# OOBDROID_V1.net
KiCad netlist of a schematic drawn in EAGLE
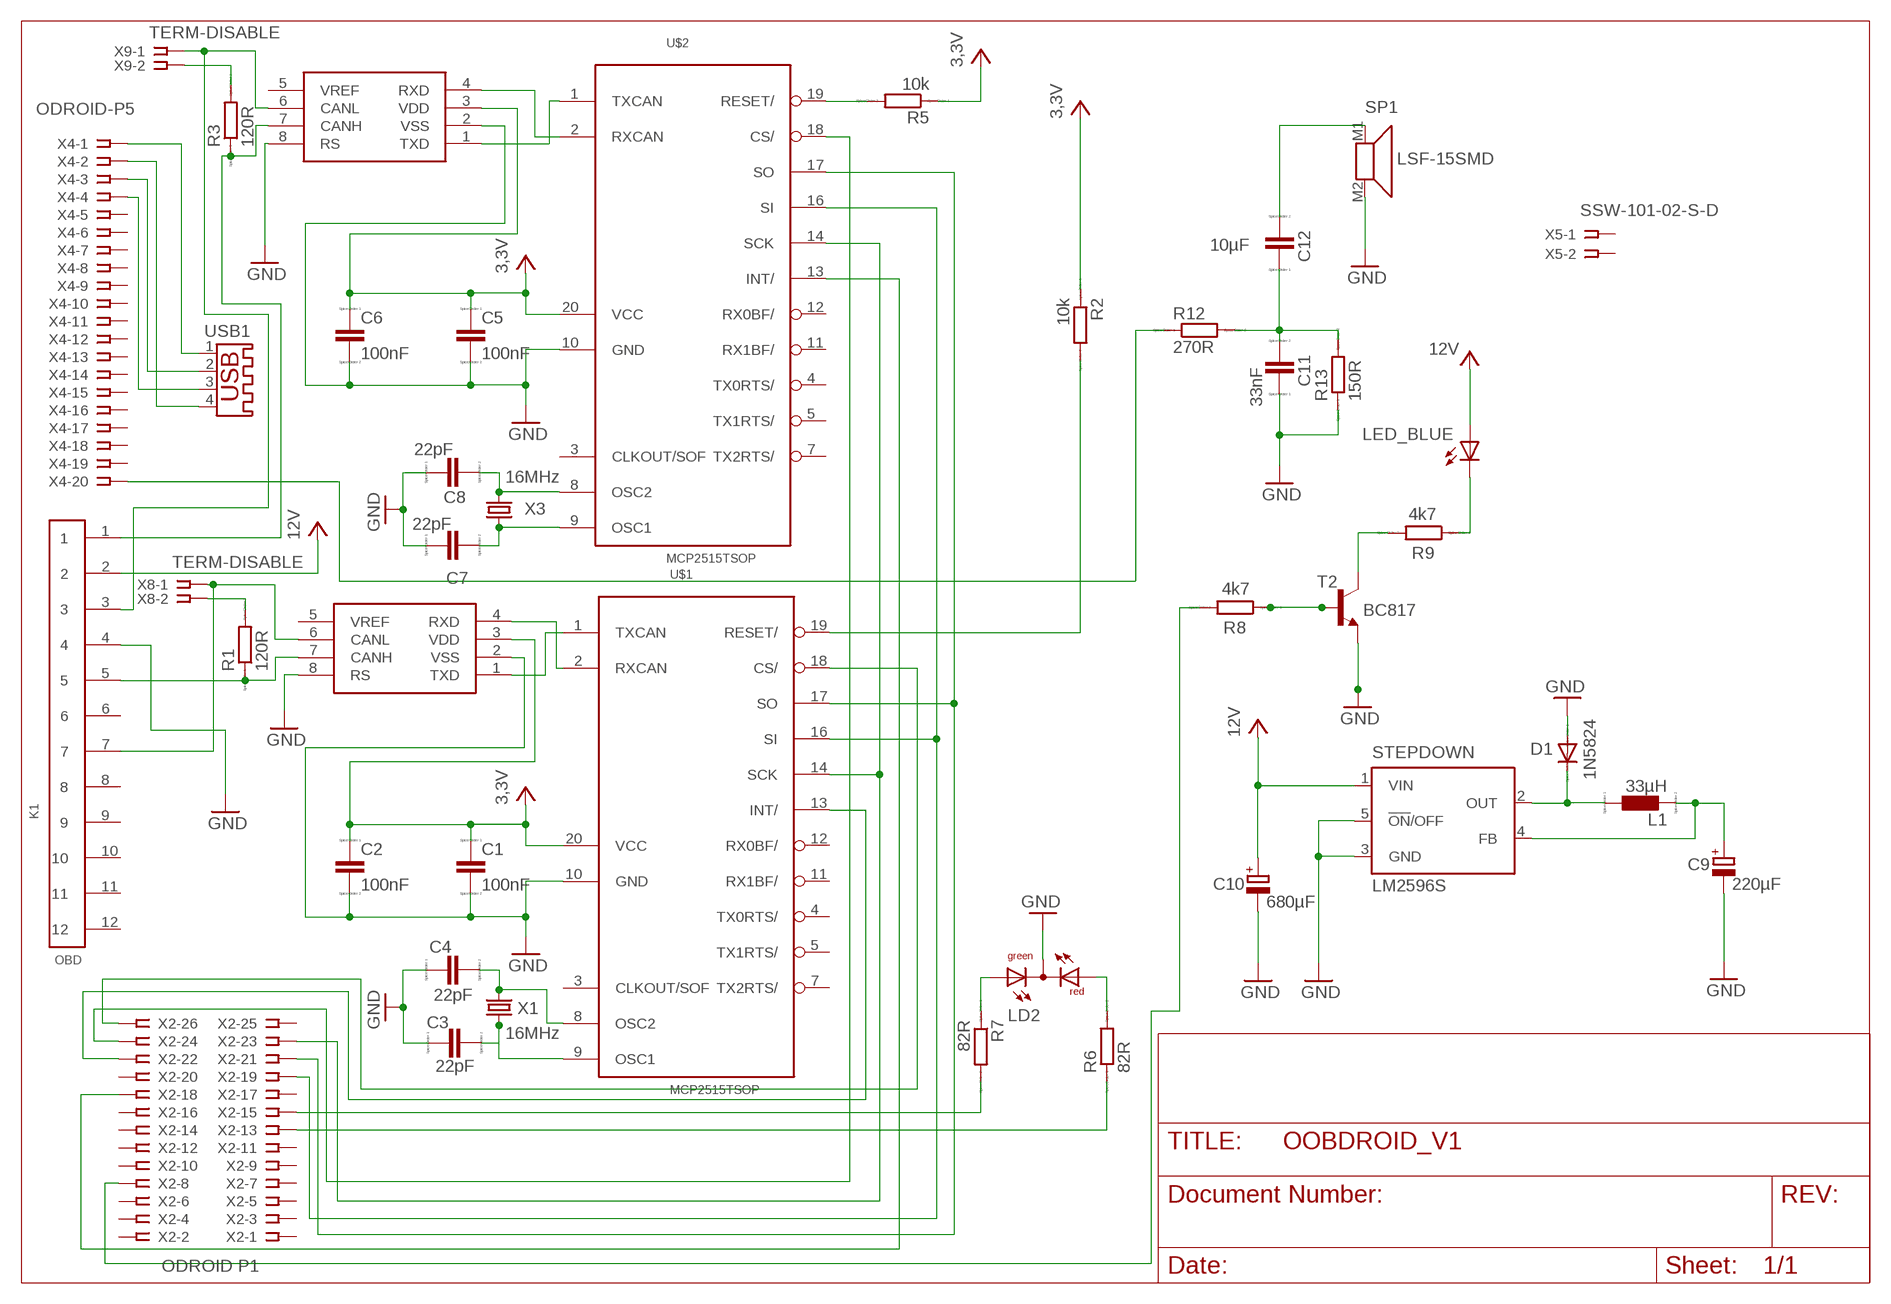
[diagram p0: schematic, sheet 1]

(export (version "E")
  (design (tool "Eeschema 10.0.6"))
  (components
    (comp (ref "C1")
      (value "100nF")
      (footprint "eagle-import:C0805")
      (libsource (lib "eagle-import") (part "C"))
    )
    (comp (ref "C2")
      (value "100nF")
      (footprint "eagle-import:C0805")
      (libsource (lib "eagle-import") (part "C"))
    )
    (comp (ref "C3")
      (value "22pF")
      (footprint "eagle-import:C0805")
      (libsource (lib "eagle-import") (part "C"))
    )
    (comp (ref "C4")
      (value "22pF")
      (footprint "eagle-import:C0805")
      (libsource (lib "eagle-import") (part "C"))
    )
    (comp (ref "C5")
      (value "100nF")
      (footprint "eagle-import:C0805")
      (libsource (lib "eagle-import") (part "C"))
    )
    (comp (ref "C6")
      (value "100nF")
      (footprint "eagle-import:C0805")
      (libsource (lib "eagle-import") (part "C"))
    )
    (comp (ref "C7")
      (value "22pF")
      (footprint "eagle-import:C0805")
      (libsource (lib "eagle-import") (part "C"))
    )
    (comp (ref "C8")
      (value "22pF")
      (footprint "eagle-import:C0805")
      (libsource (lib "eagle-import") (part "C"))
    )
    (comp (ref "C9")
      (value "220µF")
      (footprint "eagle-import:E1,8-4")
      (libsource (lib "eagle-import") (part "CPOL-EUE1.8-4"))
    )
    (comp (ref "C10")
      (value "680µF")
      (footprint "eagle-import:E1,8-4")
      (libsource (lib "eagle-import") (part "CPOL-EUE1.8-4"))
    )
    (comp (ref "C11")
      (value "33nF")
      (footprint "eagle-import:C0805")
      (libsource (lib "eagle-import") (part "C"))
    )
    (comp (ref "C12")
      (value "10µF")
      (footprint "eagle-import:C0805")
      (libsource (lib "eagle-import") (part "C"))
    )
    (comp (ref "D1")
      (value "1N5824")
      (footprint "eagle-import:DO214AA")
      (libsource (lib "eagle-import") (part "DIODE-DO214AA"))
    )
    (comp (ref "K1")
      (value "OBD")
      (footprint "eagle-import:653112124022")
      (libsource (lib "eagle-import") (part "653112124022"))
    )
    (comp (ref "L1")
      (value "33µH")
      (footprint "eagle-import:L4532P")
      (libsource (lib "eagle-import") (part "LL4532P"))
    )
    (comp (ref "LD2")
      (value "DUOLED-RG-C")
      (footprint "eagle-import:DUOLED-C-5MM")
      (libsource (lib "eagle-import") (part "DUOLED-RG-C"))
    )
    (comp (ref "LED_BLUE")
      (value "LED5MM")
      (footprint "eagle-import:LED5MM")
      (libsource (lib "eagle-import") (part "LED5MM"))
    )
    (comp (ref "R1")
      (value "120R")
      (footprint "eagle-import:R0603")
      (libsource (lib "eagle-import") (part "RR0603"))
    )
    (comp (ref "R2")
      (value "10k")
      (footprint "eagle-import:R0603")
      (libsource (lib "eagle-import") (part "RR0603"))
    )
    (comp (ref "R3")
      (value "120R")
      (footprint "eagle-import:R0603")
      (libsource (lib "eagle-import") (part "RR0603"))
    )
    (comp (ref "R5")
      (value "10k")
      (footprint "eagle-import:R0603")
      (libsource (lib "eagle-import") (part "RR0603"))
    )
    (comp (ref "R6")
      (value "82R")
      (footprint "eagle-import:R0603")
      (libsource (lib "eagle-import") (part "RR0603"))
    )
    (comp (ref "R7")
      (value "82R")
      (footprint "eagle-import:R0603")
      (libsource (lib "eagle-import") (part "RR0603"))
    )
    (comp (ref "R8")
      (value "4k7")
      (footprint "eagle-import:R0603")
      (libsource (lib "eagle-import") (part "RR0603"))
    )
    (comp (ref "R9")
      (value "4k7")
      (footprint "eagle-import:R0603")
      (libsource (lib "eagle-import") (part "RR0603"))
    )
    (comp (ref "R12")
      (value "270R")
      (footprint "eagle-import:R0603")
      (libsource (lib "eagle-import") (part "RR0603"))
    )
    (comp (ref "R13")
      (value "150R")
      (footprint "eagle-import:R0603")
      (libsource (lib "eagle-import") (part "RR0603"))
    )
    (comp (ref "SP1")
      (value "LSF-15SMD")
      (footprint "eagle-import:SMS-1308MS-2-R")
      (libsource (lib "eagle-import") (part "SMS-1308MS-2-RLSF-15SMD"))
    )
    (comp (ref "STEPDOWN")
      (value "LM2596S")
      (footprint "eagle-import:TO263-5")
      (fields (field (name "MF") "NATIONAL SEMICONDUCTOR") (field (name "MPN") "LM2596S-ADJ/NOPB"))
      (libsource (lib "eagle-import") (part "LM2596S"))
    )
    (comp (ref "T2")
      (value "BC817")
      (footprint "eagle-import:SOT23")
      (libsource (lib "eagle-import") (part "BC847"))
    )
    (comp (ref "U$1")
      (value "MCP2515TSOP")
      (footprint "eagle-import:TSSOP20")
      (libsource (lib "eagle-import") (part "MCP2515TSOP"))
    )
    (comp (ref "U$2")
      (value "MCP2515TSOP")
      (footprint "eagle-import:TSSOP20")
      (libsource (lib "eagle-import") (part "MCP2515TSOP"))
    )
    (comp (ref "U1")
      (value "MCP2551")
      (footprint "eagle-import:SO08")
      (libsource (lib "eagle-import") (part "MCP2551"))
    )
    (comp (ref "U2")
      (value "MCP2551")
      (footprint "eagle-import:SO08")
      (libsource (lib "eagle-import") (part "MCP2551"))
    )
    (comp (ref "USB1")
      (value "USB-A003")
      (footprint "eagle-import:USB-A003")
      (libsource (lib "eagle-import") (part "USB-A003"))
    )
    (comp (ref "X1")
      (value "16MHz")
      (footprint "eagle-import:HC49")
      (libsource (lib "eagle-import") (part "CRYSTALS-NOGND-HC49"))
    )
    (comp (ref "X2")
      (value "ODROID P1")
      (footprint "eagle-import:SSW-113-02-S-D")
      (fields (field (name "MPN") "SSW-113-02-S-D"))
      (libsource (lib "eagle-import") (part "SSW-113-02-S-D"))
    )
    (comp (ref "X3")
      (value "16MHz")
      (footprint "eagle-import:HC49")
      (libsource (lib "eagle-import") (part "CRYSTALS-NOGND-HC49"))
    )
    (comp (ref "X4")
      (value "ODROID-P5")
      (footprint "eagle-import:SSW-120-02-S-S")
      (fields (field (name "MPN") "SSW-120-02-S-S"))
      (libsource (lib "eagle-import") (part "SSW-120-02-S-S"))
    )
    (comp (ref "X5")
      (value "SSW-101-02-S-D")
      (footprint "eagle-import:SSW-101-02-S-D")
      (libsource (lib "eagle-import") (part "SSW-101-02-S-D"))
    )
    (comp (ref "X8")
      (value "TERM-DISABLE")
      (footprint "eagle-import:SSW-101-02-S-D")
      (fields (field (name "MPN") "SSW-101-02-S-D") (field (name "MPN_1") "CAN-DISABLE"))
      (libsource (lib "eagle-import") (part "SSW-101-02-S-D"))
    )
    (comp (ref "X9")
      (value "TERM-DISABLE")
      (footprint "eagle-import:SSW-101-02-S-D")
      (fields (field (name "MPN") "SSW-101-02-S-D"))
      (libsource (lib "eagle-import") (part "SSW-101-02-S-D"))
    )
  )
  (nets
    (net (code "1") (name "12V") (class "Default")
      (node (ref "C1") (pin "1") (pinfunction "1_1") (pintype "passive"))
      (node (ref "C10") (pin "+") (pinfunction "+_+") (pintype "passive"))
      (node (ref "C2") (pin "1") (pinfunction "1_1") (pintype "passive"))
      (node (ref "C5") (pin "1") (pinfunction "1_1") (pintype "passive"))
      (node (ref "C6") (pin "1") (pinfunction "1_1") (pintype "passive"))
      (node (ref "K1") (pin "2") (pinfunction "2_2") (pintype "bidirectional"))
      (node (ref "LED_BLUE") (pin "A") (pinfunction "A_A") (pintype "passive"))
      (node (ref "R2") (pin "1") (pinfunction "1_1") (pintype "passive"))
      (node (ref "R5") (pin "1") (pinfunction "1_1") (pintype "passive"))
      (node (ref "STEPDOWN") (pin "1") (pinfunction "VIN_1") (pintype "input"))
      (node (ref "U$1") (pin "20") (pinfunction "VCC_20") (pintype "power_in"))
      (node (ref "U$2") (pin "20") (pinfunction "VCC_20") (pintype "power_in"))
      (node (ref "U1") (pin "3") (pinfunction "VDD_3") (pintype "bidirectional"))
      (node (ref "U2") (pin "3") (pinfunction "VDD_3") (pintype "bidirectional"))
    )
    (net (code "2") (name "GND") (class "Default")
      (node (ref "C1") (pin "2") (pinfunction "2_2") (pintype "passive"))
      (node (ref "C10") (pin "-") (pinfunction "-_-") (pintype "passive"))
      (node (ref "C11") (pin "1") (pinfunction "1_1") (pintype "passive"))
      (node (ref "C2") (pin "2") (pinfunction "2_2") (pintype "passive"))
      (node (ref "C3") (pin "1") (pinfunction "1_1") (pintype "passive"))
      (node (ref "C4") (pin "1") (pinfunction "1_1") (pintype "passive"))
      (node (ref "C5") (pin "2") (pinfunction "2_2") (pintype "passive"))
      (node (ref "C6") (pin "2") (pinfunction "2_2") (pintype "passive"))
      (node (ref "C7") (pin "1") (pinfunction "1_1") (pintype "passive"))
      (node (ref "C8") (pin "1") (pinfunction "1_1") (pintype "passive"))
      (node (ref "C9") (pin "-") (pinfunction "-_-") (pintype "passive"))
      (node (ref "D1") (pin "A") (pinfunction "A_A") (pintype "passive"))
      (node (ref "K1") (pin "4") (pinfunction "4_4") (pintype "bidirectional"))
      (node (ref "LD2") (pin "C") (pinfunction "C_C") (pintype "passive"))
      (node (ref "R13") (pin "1") (pinfunction "1_1") (pintype "passive"))
      (node (ref "SP1") (pin "M2") (pinfunction "2_M2") (pintype "passive"))
      (node (ref "STEPDOWN") (pin "3") (pinfunction "GND_3") (pintype "power_in"))
      (node (ref "STEPDOWN") (pin "5") (pinfunction "~{ON}/OFF_5") (pintype "input"))
      (node (ref "T2") (pin "2") (pinfunction "E_2") (pintype "passive"))
      (node (ref "U$1") (pin "10") (pinfunction "GND_10") (pintype "power_in"))
      (node (ref "U$2") (pin "10") (pinfunction "GND_10") (pintype "power_in"))
      (node (ref "U1") (pin "2") (pinfunction "VSS_2") (pintype "bidirectional"))
      (node (ref "U1") (pin "8") (pinfunction "RS_8") (pintype "bidirectional"))
      (node (ref "U2") (pin "2") (pinfunction "VSS_2") (pintype "bidirectional"))
      (node (ref "U2") (pin "8") (pinfunction "RS_8") (pintype "bidirectional"))
    )
    (net (code "3") (name "Net-(C11-Pad2)") (class "Default")
      (node (ref "C11") (pin "2") (pinfunction "2_2") (pintype "passive"))
      (node (ref "C12") (pin "1") (pinfunction "1_1") (pintype "passive"))
      (node (ref "R12") (pin "2") (pinfunction "2_2") (pintype "passive"))
      (node (ref "R13") (pin "2") (pinfunction "2_2") (pintype "passive"))
    )
    (net (code "4") (name "Net-(LD2-AG)") (class "Default")
      (node (ref "LD2") (pin "AX") (pinfunction "AG_AX") (pintype "passive"))
      (node (ref "R7") (pin "1") (pinfunction "1_1") (pintype "passive"))
    )
    (net (code "5") (name "Net-(LD2-PadAR)") (class "Default")
      (node (ref "LD2") (pin "AR") (pinfunction "AR_AR") (pintype "passive"))
      (node (ref "R6") (pin "2") (pinfunction "2_2") (pintype "passive"))
    )
    (net (code "6") (name "Net-(LED_BLUE-C)") (class "Default")
      (node (ref "LED_BLUE") (pin "K") (pinfunction "C_K") (pintype "passive"))
      (node (ref "R9") (pin "1") (pinfunction "1_1") (pintype "passive"))
    )
    (net (code "7") (name "Net-(SP1-1)") (class "Default")
      (node (ref "C12") (pin "2") (pinfunction "2_2") (pintype "passive"))
      (node (ref "SP1") (pin "M1") (pinfunction "1_M1") (pintype "passive"))
    )
    (net (code "8") (name "Net-(STEPDOWN-FB)") (class "Default")
      (node (ref "C9") (pin "+") (pinfunction "+_+") (pintype "passive"))
      (node (ref "L1") (pin "2") (pinfunction "2_2") (pintype "passive"))
      (node (ref "STEPDOWN") (pin "4") (pinfunction "FB_4") (pintype "input"))
    )
    (net (code "9") (name "Net-(STEPDOWN-OUT)") (class "Default")
      (node (ref "D1") (pin "C") (pinfunction "C_C") (pintype "passive"))
      (node (ref "L1") (pin "1") (pinfunction "1_1") (pintype "passive"))
      (node (ref "STEPDOWN") (pin "2") (pinfunction "OUT_2") (pintype "output"))
    )
    (net (code "10") (name "Net-(T2-B)") (class "Default")
      (node (ref "R8") (pin "1") (pinfunction "1_1") (pintype "passive"))
      (node (ref "T2") (pin "1") (pinfunction "B_1") (pintype "passive"))
    )
    (net (code "11") (name "Net-(T2-C)") (class "Default")
      (node (ref "R9") (pin "2") (pinfunction "2_2") (pintype "passive"))
      (node (ref "T2") (pin "3") (pinfunction "C_3") (pintype "passive"))
    )
    (net (code "12") (name "Net-(U$1-CS{slash})") (class "Default")
      (node (ref "U$1") (pin "18") (pinfunction "CS/_18") (pintype "input"))
      (node (ref "X2") (pin "26") (pinfunction "1_26") (pintype "passive"))
    )
    (net (code "13") (name "Net-(U$1-INT{slash})") (class "Default")
      (node (ref "U$1") (pin "13") (pinfunction "INT/_13") (pintype "output"))
      (node (ref "X2") (pin "22") (pinfunction "1_22") (pintype "passive"))
    )
    (net (code "14") (name "Net-(U$1-OSC1)") (class "Default")
      (node (ref "C3") (pin "2") (pinfunction "2_2") (pintype "passive"))
      (node (ref "U$1") (pin "9") (pinfunction "OSC1_9") (pintype "bidirectional"))
      (node (ref "X1") (pin "1") (pinfunction "1_1") (pintype "passive"))
    )
    (net (code "15") (name "Net-(U$1-OSC2)") (class "Default")
      (node (ref "C4") (pin "2") (pinfunction "2_2") (pintype "passive"))
      (node (ref "U$1") (pin "8") (pinfunction "OSC2_8") (pintype "bidirectional"))
      (node (ref "X1") (pin "2") (pinfunction "2_2") (pintype "passive"))
    )
    (net (code "16") (name "Net-(U$1-RESET{slash})") (class "Default")
      (node (ref "R2") (pin "2") (pinfunction "2_2") (pintype "passive"))
      (node (ref "U$1") (pin "19") (pinfunction "RESET/_19") (pintype "input"))
    )
    (net (code "17") (name "Net-(U$1-RXCAN)") (class "Default")
      (node (ref "U$1") (pin "2") (pinfunction "RXCAN_2") (pintype "input"))
      (node (ref "U1") (pin "4") (pinfunction "RXD_4") (pintype "bidirectional"))
    )
    (net (code "18") (name "Net-(U$1-SCK)") (class "Default")
      (node (ref "U$1") (pin "14") (pinfunction "SCK_14") (pintype "input"))
      (node (ref "U$2") (pin "14") (pinfunction "SCK_14") (pintype "input"))
      (node (ref "X2") (pin "23") (pinfunction "1_23") (pintype "passive"))
    )
    (net (code "19") (name "Net-(U$1-SI)") (class "Default")
      (node (ref "U$1") (pin "16") (pinfunction "SI_16") (pintype "input"))
      (node (ref "U$2") (pin "16") (pinfunction "SI_16") (pintype "input"))
      (node (ref "X2") (pin "19") (pinfunction "1_19") (pintype "passive"))
    )
    (net (code "20") (name "Net-(U$1-SO)") (class "Default")
      (node (ref "U$1") (pin "17") (pinfunction "SO_17") (pintype "output"))
      (node (ref "U$2") (pin "17") (pinfunction "SO_17") (pintype "output"))
      (node (ref "X2") (pin "21") (pinfunction "1_21") (pintype "passive"))
    )
    (net (code "21") (name "Net-(U$1-TXCAN)") (class "Default")
      (node (ref "U$1") (pin "1") (pinfunction "TXCAN_1") (pintype "output"))
      (node (ref "U1") (pin "1") (pinfunction "TXD_1") (pintype "bidirectional"))
    )
    (net (code "22") (name "Net-(U$2-CS{slash})") (class "Default")
      (node (ref "U$2") (pin "18") (pinfunction "CS/_18") (pintype "input"))
      (node (ref "X2") (pin "24") (pinfunction "1_24") (pintype "passive"))
    )
    (net (code "23") (name "Net-(U$2-INT{slash})") (class "Default")
      (node (ref "U$2") (pin "13") (pinfunction "INT/_13") (pintype "output"))
      (node (ref "X2") (pin "18") (pinfunction "1_18") (pintype "passive"))
    )
    (net (code "24") (name "Net-(U$2-OSC1)") (class "Default")
      (node (ref "C7") (pin "2") (pinfunction "2_2") (pintype "passive"))
      (node (ref "U$2") (pin "9") (pinfunction "OSC1_9") (pintype "bidirectional"))
      (node (ref "X3") (pin "1") (pinfunction "1_1") (pintype "passive"))
    )
    (net (code "25") (name "Net-(U$2-OSC2)") (class "Default")
      (node (ref "C8") (pin "2") (pinfunction "2_2") (pintype "passive"))
      (node (ref "U$2") (pin "8") (pinfunction "OSC2_8") (pintype "bidirectional"))
      (node (ref "X3") (pin "2") (pinfunction "2_2") (pintype "passive"))
    )
    (net (code "26") (name "Net-(U$2-RESET{slash})") (class "Default")
      (node (ref "R5") (pin "2") (pinfunction "2_2") (pintype "passive"))
      (node (ref "U$2") (pin "19") (pinfunction "RESET/_19") (pintype "input"))
    )
    (net (code "27") (name "Net-(U$2-RXCAN)") (class "Default")
      (node (ref "U$2") (pin "2") (pinfunction "RXCAN_2") (pintype "input"))
      (node (ref "U2") (pin "4") (pinfunction "RXD_4") (pintype "bidirectional"))
    )
    (net (code "28") (name "Net-(U$2-TXCAN)") (class "Default")
      (node (ref "U$2") (pin "1") (pinfunction "TXCAN_1") (pintype "output"))
      (node (ref "U2") (pin "1") (pinfunction "TXD_1") (pintype "bidirectional"))
    )
    (net (code "29") (name "Net-(U1-CANH)") (class "Default")
      (node (ref "K1") (pin "5") (pinfunction "5_5") (pintype "bidirectional"))
      (node (ref "R1") (pin "1") (pinfunction "1_1") (pintype "passive"))
      (node (ref "U1") (pin "7") (pinfunction "CANH_7") (pintype "bidirectional"))
    )
    (net (code "30") (name "Net-(U1-CANL)") (class "Default")
      (node (ref "K1") (pin "7") (pinfunction "7_7") (pintype "bidirectional"))
      (node (ref "U1") (pin "6") (pinfunction "CANL_6") (pintype "bidirectional"))
      (node (ref "X8") (pin "1") (pinfunction "1_1") (pintype "passive"))
    )
    (net (code "31") (name "Net-(U2-CANH)") (class "Default")
      (node (ref "K1") (pin "1") (pinfunction "1_1") (pintype "bidirectional"))
      (node (ref "R3") (pin "1") (pinfunction "1_1") (pintype "passive"))
      (node (ref "U2") (pin "7") (pinfunction "CANH_7") (pintype "bidirectional"))
    )
    (net (code "32") (name "Net-(U2-CANL)") (class "Default")
      (node (ref "K1") (pin "3") (pinfunction "3_3") (pintype "bidirectional"))
      (node (ref "U2") (pin "6") (pinfunction "CANL_6") (pintype "bidirectional"))
      (node (ref "X9") (pin "1") (pinfunction "1_1") (pintype "passive"))
    )
    (net (code "33") (name "Net-(USB1-Pad1)") (class "Default")
      (node (ref "USB1") (pin "1") (pinfunction "1_1") (pintype "passive"))
      (node (ref "X4") (pin "1") (pinfunction "1_1") (pintype "passive"))
    )
    (net (code "34") (name "Net-(X2E-1)") (class "Default")
      (node (ref "R6") (pin "1") (pinfunction "1_1") (pintype "passive"))
      (node (ref "X2") (pin "13") (pinfunction "1_13") (pintype "passive"))
    )
    (net (code "35") (name "Net-(X2G-1)") (class "Default")
      (node (ref "R7") (pin "2") (pinfunction "2_2") (pintype "passive"))
      (node (ref "X2") (pin "15") (pinfunction "1_15") (pintype "passive"))
    )
    (net (code "36") (name "Net-(X2Y-1)") (class "Default")
      (node (ref "R8") (pin "2") (pinfunction "2_2") (pintype "passive"))
      (node (ref "X2") (pin "8") (pinfunction "1_8") (pintype "passive"))
    )
    (net (code "37") (name "Net-(X4L-1)") (class "Default")
      (node (ref "USB1") (pin "4") (pinfunction "4_4") (pintype "passive"))
      (node (ref "X4") (pin "2") (pinfunction "1_2") (pintype "passive"))
    )
    (net (code "38") (name "Net-(X4M-1)") (class "Default")
      (node (ref "R12") (pin "1") (pinfunction "1_1") (pintype "passive"))
      (node (ref "X4") (pin "20") (pinfunction "1_20") (pintype "passive"))
    )
    (net (code "39") (name "Net-(X4N-1)") (class "Default")
      (node (ref "USB1") (pin "2") (pinfunction "2_2") (pintype "passive"))
      (node (ref "X4") (pin "3") (pinfunction "1_3") (pintype "passive"))
    )
    (net (code "40") (name "Net-(X4O-1)") (class "Default")
      (node (ref "USB1") (pin "3") (pinfunction "3_3") (pintype "passive"))
      (node (ref "X4") (pin "4") (pinfunction "1_4") (pintype "passive"))
    )
    (net (code "41") (name "Net-(X8B-1)") (class "Default")
      (node (ref "R1") (pin "2") (pinfunction "2_2") (pintype "passive"))
      (node (ref "X8") (pin "2") (pinfunction "1_2") (pintype "passive"))
    )
    (net (code "42") (name "Net-(X9B-1)") (class "Default")
      (node (ref "R3") (pin "2") (pinfunction "2_2") (pintype "passive"))
      (node (ref "X9") (pin "2") (pinfunction "1_2") (pintype "passive"))
    )
    (net (code "43") (name "unconnected-(K1-Pad6)") (class "Default")
      (node (ref "K1") (pin "6") (pinfunction "6_6") (pintype "bidirectional"))
    )
    (net (code "44") (name "unconnected-(K1-Pad8)") (class "Default")
      (node (ref "K1") (pin "8") (pinfunction "8_8") (pintype "bidirectional"))
    )
    (net (code "45") (name "unconnected-(K1-Pad9)") (class "Default")
      (node (ref "K1") (pin "9") (pinfunction "9_9") (pintype "bidirectional"))
    )
    (net (code "46") (name "unconnected-(K1-Pad10)") (class "Default")
      (node (ref "K1") (pin "10") (pinfunction "10_10") (pintype "bidirectional"))
    )
    (net (code "47") (name "unconnected-(K1-Pad11)") (class "Default")
      (node (ref "K1") (pin "11") (pinfunction "11_11") (pintype "bidirectional"))
    )
    (net (code "48") (name "unconnected-(K1-Pad12)") (class "Default")
      (node (ref "K1") (pin "12") (pinfunction "12_12") (pintype "bidirectional"))
    )
    (net (code "49") (name "unconnected-(U$1-CLKOUT{slash}SOF-Pad3)") (class "Default")
      (node (ref "U$1") (pin "3") (pinfunction "CLKOUT/SOF_3") (pintype "bidirectional"))
    )
    (net (code "50") (name "unconnected-(U$1-RX0BF{slash}-Pad12)") (class "Default")
      (node (ref "U$1") (pin "12") (pinfunction "RX0BF/_12") (pintype "bidirectional"))
    )
    (net (code "51") (name "unconnected-(U$1-RX1BF{slash}-Pad11)") (class "Default")
      (node (ref "U$1") (pin "11") (pinfunction "RX1BF/_11") (pintype "bidirectional"))
    )
    (net (code "52") (name "unconnected-(U$1-TX0RTS{slash}-Pad4)") (class "Default")
      (node (ref "U$1") (pin "4") (pinfunction "TX0RTS/_4") (pintype "bidirectional"))
    )
    (net (code "53") (name "unconnected-(U$1-TX1RTS{slash}-Pad5)") (class "Default")
      (node (ref "U$1") (pin "5") (pinfunction "TX1RTS/_5") (pintype "bidirectional"))
    )
    (net (code "54") (name "unconnected-(U$1-TX2RTS{slash}-Pad7)") (class "Default")
      (node (ref "U$1") (pin "7") (pinfunction "TX2RTS/_7") (pintype "bidirectional"))
    )
    (net (code "55") (name "unconnected-(U$2-CLKOUT{slash}SOF-Pad3)") (class "Default")
      (node (ref "U$2") (pin "3") (pinfunction "CLKOUT/SOF_3") (pintype "bidirectional"))
    )
    (net (code "56") (name "unconnected-(U$2-RX0BF{slash}-Pad12)") (class "Default")
      (node (ref "U$2") (pin "12") (pinfunction "RX0BF/_12") (pintype "bidirectional"))
    )
    (net (code "57") (name "unconnected-(U$2-RX1BF{slash}-Pad11)") (class "Default")
      (node (ref "U$2") (pin "11") (pinfunction "RX1BF/_11") (pintype "bidirectional"))
    )
    (net (code "58") (name "unconnected-(U$2-TX0RTS{slash}-Pad4)") (class "Default")
      (node (ref "U$2") (pin "4") (pinfunction "TX0RTS/_4") (pintype "bidirectional"))
    )
    (net (code "59") (name "unconnected-(U$2-TX1RTS{slash}-Pad5)") (class "Default")
      (node (ref "U$2") (pin "5") (pinfunction "TX1RTS/_5") (pintype "bidirectional"))
    )
    (net (code "60") (name "unconnected-(U$2-TX2RTS{slash}-Pad7)") (class "Default")
      (node (ref "U$2") (pin "7") (pinfunction "TX2RTS/_7") (pintype "bidirectional"))
    )
    (net (code "61") (name "unconnected-(U1-VREF-Pad5)") (class "Default")
      (node (ref "U1") (pin "5") (pinfunction "VREF_5") (pintype "bidirectional"))
    )
    (net (code "62") (name "unconnected-(U2-VREF-Pad5)") (class "Default")
      (node (ref "U2") (pin "5") (pinfunction "VREF_5") (pintype "bidirectional"))
    )
    (net (code "63") (name "unconnected-(X2-Pad1)") (class "Default")
      (node (ref "X2") (pin "1") (pinfunction "1_1") (pintype "passive"))
    )
    (net (code "64") (name "unconnected-(X2B-1-Pad10)") (class "Default")
      (node (ref "X2") (pin "10") (pinfunction "1_10") (pintype "passive"))
    )
    (net (code "65") (name "unconnected-(X2C-1-Pad11)") (class "Default")
      (node (ref "X2") (pin "11") (pinfunction "1_11") (pintype "passive"))
    )
    (net (code "66") (name "unconnected-(X2D-1-Pad12)") (class "Default")
      (node (ref "X2") (pin "12") (pinfunction "1_12") (pintype "passive"))
    )
    (net (code "67") (name "unconnected-(X2F-1-Pad14)") (class "Default")
      (node (ref "X2") (pin "14") (pinfunction "1_14") (pintype "passive"))
    )
    (net (code "68") (name "unconnected-(X2H-1-Pad16)") (class "Default")
      (node (ref "X2") (pin "16") (pinfunction "1_16") (pintype "passive"))
    )
    (net (code "69") (name "unconnected-(X2I-1-Pad17)") (class "Default")
      (node (ref "X2") (pin "17") (pinfunction "1_17") (pintype "passive"))
    )
    (net (code "70") (name "unconnected-(X2L-1-Pad2)") (class "Default")
      (node (ref "X2") (pin "2") (pinfunction "1_2") (pintype "passive"))
    )
    (net (code "71") (name "unconnected-(X2M-1-Pad20)") (class "Default")
      (node (ref "X2") (pin "20") (pinfunction "1_20") (pintype "passive"))
    )
    (net (code "72") (name "unconnected-(X2R-1-Pad25)") (class "Default")
      (node (ref "X2") (pin "25") (pinfunction "1_25") (pintype "passive"))
    )
    (net (code "73") (name "unconnected-(X2T-1-Pad3)") (class "Default")
      (node (ref "X2") (pin "3") (pinfunction "1_3") (pintype "passive"))
    )
    (net (code "74") (name "unconnected-(X2U-1-Pad4)") (class "Default")
      (node (ref "X2") (pin "4") (pinfunction "1_4") (pintype "passive"))
    )
    (net (code "75") (name "unconnected-(X2V-1-Pad5)") (class "Default")
      (node (ref "X2") (pin "5") (pinfunction "1_5") (pintype "passive"))
    )
    (net (code "76") (name "unconnected-(X2W-1-Pad6)") (class "Default")
      (node (ref "X2") (pin "6") (pinfunction "1_6") (pintype "passive"))
    )
    (net (code "77") (name "unconnected-(X2X-1-Pad7)") (class "Default")
      (node (ref "X2") (pin "7") (pinfunction "1_7") (pintype "passive"))
    )
    (net (code "78") (name "unconnected-(X2Z-1-Pad9)") (class "Default")
      (node (ref "X2") (pin "9") (pinfunction "1_9") (pintype "passive"))
    )
    (net (code "79") (name "unconnected-(X4B-1-Pad10)") (class "Default")
      (node (ref "X4") (pin "10") (pinfunction "1_10") (pintype "passive"))
    )
    (net (code "80") (name "unconnected-(X4C-1-Pad11)") (class "Default")
      (node (ref "X4") (pin "11") (pinfunction "1_11") (pintype "passive"))
    )
    (net (code "81") (name "unconnected-(X4D-1-Pad12)") (class "Default")
      (node (ref "X4") (pin "12") (pinfunction "1_12") (pintype "passive"))
    )
    (net (code "82") (name "unconnected-(X4E-1-Pad13)") (class "Default")
      (node (ref "X4") (pin "13") (pinfunction "1_13") (pintype "passive"))
    )
    (net (code "83") (name "unconnected-(X4F-1-Pad14)") (class "Default")
      (node (ref "X4") (pin "14") (pinfunction "1_14") (pintype "passive"))
    )
    (net (code "84") (name "unconnected-(X4G-1-Pad15)") (class "Default")
      (node (ref "X4") (pin "15") (pinfunction "1_15") (pintype "passive"))
    )
    (net (code "85") (name "unconnected-(X4H-1-Pad16)") (class "Default")
      (node (ref "X4") (pin "16") (pinfunction "1_16") (pintype "passive"))
    )
    (net (code "86") (name "unconnected-(X4I-1-Pad17)") (class "Default")
      (node (ref "X4") (pin "17") (pinfunction "1_17") (pintype "passive"))
    )
    (net (code "87") (name "unconnected-(X4J-1-Pad18)") (class "Default")
      (node (ref "X4") (pin "18") (pinfunction "1_18") (pintype "passive"))
    )
    (net (code "88") (name "unconnected-(X4K-1-Pad19)") (class "Default")
      (node (ref "X4") (pin "19") (pinfunction "1_19") (pintype "passive"))
    )
    (net (code "89") (name "unconnected-(X4P-1-Pad5)") (class "Default")
      (node (ref "X4") (pin "5") (pinfunction "1_5") (pintype "passive"))
    )
    (net (code "90") (name "unconnected-(X4Q-1-Pad6)") (class "Default")
      (node (ref "X4") (pin "6") (pinfunction "1_6") (pintype "passive"))
    )
    (net (code "91") (name "unconnected-(X4R-1-Pad7)") (class "Default")
      (node (ref "X4") (pin "7") (pinfunction "1_7") (pintype "passive"))
    )
    (net (code "92") (name "unconnected-(X4S-1-Pad8)") (class "Default")
      (node (ref "X4") (pin "8") (pinfunction "1_8") (pintype "passive"))
    )
    (net (code "93") (name "unconnected-(X4T-1-Pad9)") (class "Default")
      (node (ref "X4") (pin "9") (pinfunction "1_9") (pintype "passive"))
    )
    (net (code "94") (name "unconnected-(X5-Pad1)") (class "Default")
      (node (ref "X5") (pin "1") (pinfunction "1_1") (pintype "passive"))
    )
    (net (code "95") (name "unconnected-(X5B-1-Pad2)") (class "Default")
      (node (ref "X5") (pin "2") (pinfunction "1_2") (pintype "passive"))
    )
  )
)
